# nrf52840-breakout-qwiic-lipo.net
KiCad netlist of a schematic drawn in EAGLE
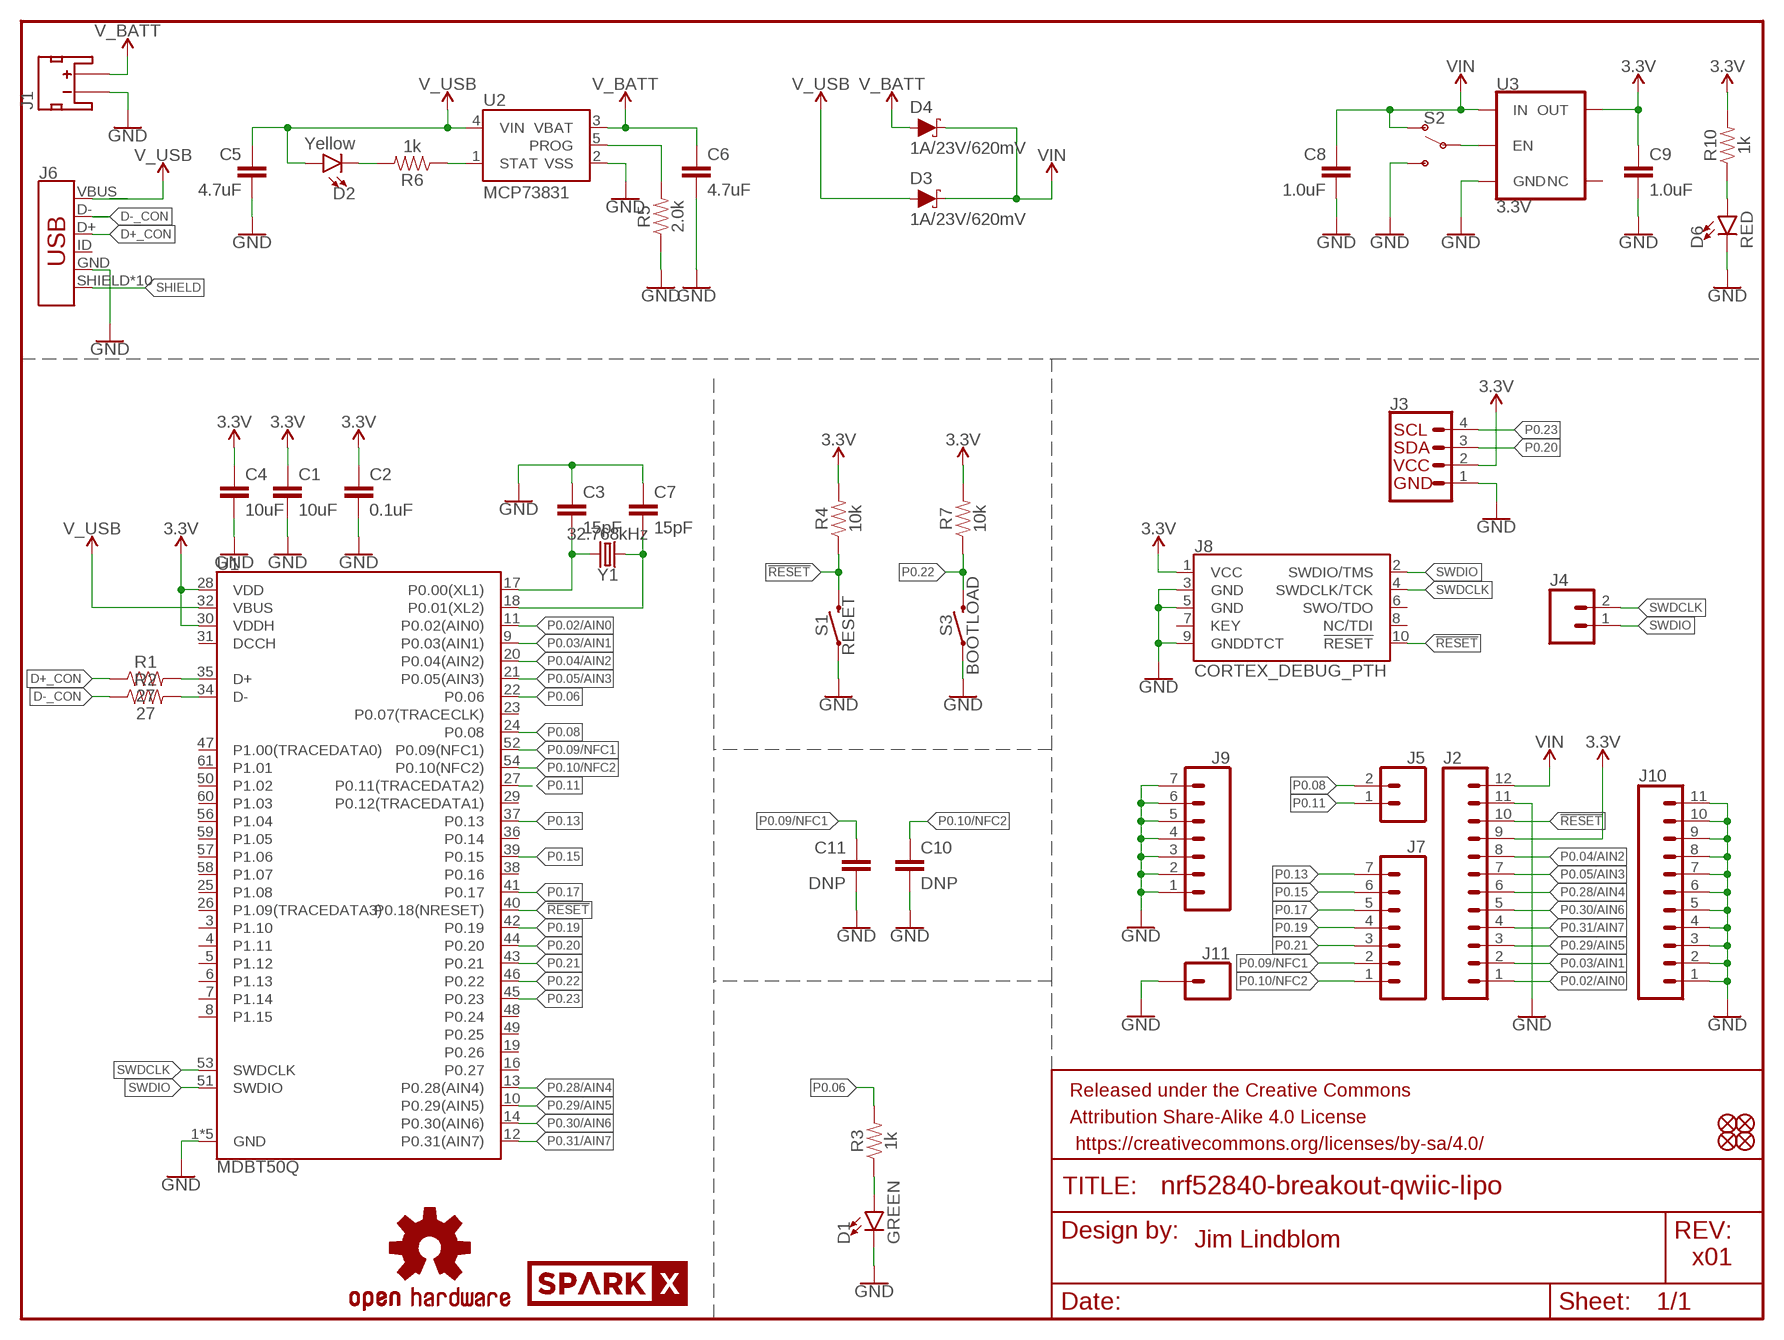
[diagram p0: schematic, sheet 1]

(export (version "E")
  (design (tool "Eeschema 10.0.6"))
  (components
    (comp (ref "C1")
      (value "10uF")
      (footprint "eagle-import:0603")
      (libsource (lib "eagle-import") (part "10UF-0603-6.3V-20%"))
    )
    (comp (ref "C2")
      (value "0.1uF")
      (footprint "eagle-import:0603")
      (libsource (lib "eagle-import") (part "0.1UF-0603-25V-(+80/-20%)"))
    )
    (comp (ref "C3")
      (value "15pF")
      (footprint "eagle-import:0603")
      (libsource (lib "eagle-import") (part "15PF-0603-50V-5%"))
    )
    (comp (ref "C4")
      (value "10uF")
      (footprint "eagle-import:0603")
      (libsource (lib "eagle-import") (part "10UF-0603-6.3V-20%"))
    )
    (comp (ref "C5")
      (value "4.7uF")
      (footprint "eagle-import:0603")
      (libsource (lib "eagle-import") (part "4.7UF-0603-6.3V-(10%)"))
    )
    (comp (ref "C6")
      (value "4.7uF")
      (footprint "eagle-import:0603")
      (libsource (lib "eagle-import") (part "4.7UF-0603-6.3V-(10%)"))
    )
    (comp (ref "C7")
      (value "15pF")
      (footprint "eagle-import:0603")
      (libsource (lib "eagle-import") (part "15PF-0603-50V-5%"))
    )
    (comp (ref "C8")
      (value "1.0uF")
      (footprint "eagle-import:0603")
      (libsource (lib "eagle-import") (part "1.0UF-0603-16V-10%"))
    )
    (comp (ref "C9")
      (value "1.0uF")
      (footprint "eagle-import:0603")
      (libsource (lib "eagle-import") (part "1.0UF-0603-16V-10%"))
    )
    (comp (ref "C10")
      (value "DNP")
      (footprint "eagle-import:0603")
      (libsource (lib "eagle-import") (part "270PF-0603-50V-5%"))
    )
    (comp (ref "C11")
      (value "DNP")
      (footprint "eagle-import:0603")
      (libsource (lib "eagle-import") (part "270PF-0603-50V-5%"))
    )
    (comp (ref "D1")
      (value "GREEN")
      (footprint "eagle-import:LED-0603")
      (libsource (lib "eagle-import") (part "LED-GREEN0603"))
    )
    (comp (ref "D2")
      (value "Yellow")
      (footprint "eagle-import:LED-0603")
      (libsource (lib "eagle-import") (part "LED-YELLOW0603"))
    )
    (comp (ref "D3")
      (value "1A/23V/620mV")
      (footprint "eagle-import:SOD-323")
      (libsource (lib "eagle-import") (part "DIODE-SCHOTTKY-BAT20J"))
    )
    (comp (ref "D4")
      (value "1A/23V/620mV")
      (footprint "eagle-import:SOD-323")
      (libsource (lib "eagle-import") (part "DIODE-SCHOTTKY-BAT20J"))
    )
    (comp (ref "D6")
      (value "RED")
      (footprint "eagle-import:LED-0603")
      (libsource (lib "eagle-import") (part "LED-RED0603"))
    )
    (comp (ref "FD1")
      (value "FIDUCIALUFIDUCIAL")
      (footprint "eagle-import:FIDUCIAL-MICRO")
      (libsource (lib "eagle-import") (part "FIDUCIALUFIDUCIAL"))
    )
    (comp (ref "FD2")
      (value "FIDUCIALUFIDUCIAL")
      (footprint "eagle-import:FIDUCIAL-MICRO")
      (libsource (lib "eagle-import") (part "FIDUCIALUFIDUCIAL"))
    )
    (comp (ref "FD3")
      (value "FIDUCIALUFIDUCIAL")
      (footprint "eagle-import:FIDUCIAL-MICRO")
      (libsource (lib "eagle-import") (part "FIDUCIALUFIDUCIAL"))
    )
    (comp (ref "FD4")
      (value "FIDUCIALUFIDUCIAL")
      (footprint "eagle-import:FIDUCIAL-MICRO")
      (libsource (lib "eagle-import") (part "FIDUCIALUFIDUCIAL"))
    )
    (comp (ref "FRAME1")
      (value "FRAME-LETTER")
      (footprint "eagle-import:CREATIVE_COMMONS")
      (libsource (lib "eagle-import") (part "FRAME-LETTER"))
    )
    (comp (ref "J1")
      (value "JST_2MM_MALESMD")
      (footprint "eagle-import:JST-2-SMD")
      (libsource (lib "eagle-import") (part "JST_2MM_MALESMD"))
    )
    (comp (ref "J2")
      (value "CONN_12NO_SILK")
      (footprint "eagle-import:1X12_NO_SILK")
      (libsource (lib "eagle-import") (part "CONN_12NO_SILK"))
    )
    (comp (ref "J3")
      (value "QWIIC_CONNECTORJS-1MM")
      (footprint "eagle-import:1X04_1MM_RA")
      (libsource (lib "eagle-import") (part "QWIIC_CONNECTORJS-1MM"))
    )
    (comp (ref "J4")
      (value "CONN_021X02_NO_SILK")
      (footprint "eagle-import:1X02_NO_SILK")
      (libsource (lib "eagle-import") (part "CONN_021X02_NO_SILK"))
    )
    (comp (ref "J5")
      (value "CONN_021X02_NO_SILK")
      (footprint "eagle-import:1X02_NO_SILK")
      (libsource (lib "eagle-import") (part "CONN_021X02_NO_SILK"))
    )
    (comp (ref "J6")
      (value "USB_MICRO-B_HALF_PTH_MILL")
      (footprint "eagle-import:USB-MICROB-PTH-MILL")
      (libsource (lib "eagle-import") (part "USB_MICRO-B_HALF_PTH_MILL"))
    )
    (comp (ref "J7")
      (value "CONN_07NO_SILK")
      (footprint "eagle-import:1X07_NO_SILK")
      (libsource (lib "eagle-import") (part "CONN_07NO_SILK"))
    )
    (comp (ref "J8")
      (value "CORTEX_DEBUG_PTH")
      (footprint "eagle-import:2X5-PTH-1.27MM")
      (libsource (lib "eagle-import") (part "CORTEX_DEBUG_PTH"))
    )
    (comp (ref "J9")
      (value "CONN_07NO_SILK")
      (footprint "eagle-import:1X07_NO_SILK")
      (libsource (lib "eagle-import") (part "CONN_07NO_SILK"))
    )
    (comp (ref "J10")
      (value "CONN_111X11_NO_SILK")
      (footprint "eagle-import:1X11_NO_SILK")
      (libsource (lib "eagle-import") (part "CONN_111X11_NO_SILK"))
    )
    (comp (ref "J11")
      (value "CONN_01PTH_NO_SILK_YES_STOP")
      (footprint "eagle-import:1X01_NO_SILK")
      (libsource (lib "eagle-import") (part "CONN_01PTH_NO_SILK_YES_STOP"))
    )
    (comp (ref "LOGO1")
      (value "SPARKX-LOGO3")
      (footprint "eagle-import:SPARKX-SMALL")
      (libsource (lib "eagle-import") (part "SPARKX-LOGO3"))
    )
    (comp (ref "LOGO2")
      (value "OSHW-LOGOM")
      (footprint "eagle-import:OSHW-LOGO-M")
      (libsource (lib "eagle-import") (part "OSHW-LOGOM"))
    )
    (comp (ref "R1")
      (value "27")
      (footprint "eagle-import:0603")
      (libsource (lib "eagle-import") (part "27OHM-0603-1/10W-1%"))
    )
    (comp (ref "R2")
      (value "27")
      (footprint "eagle-import:0603")
      (libsource (lib "eagle-import") (part "27OHM-0603-1/10W-1%"))
    )
    (comp (ref "R3")
      (value "1k")
      (footprint "eagle-import:0603")
      (libsource (lib "eagle-import") (part "1KOHM-0603-1/10W-1%"))
    )
    (comp (ref "R4")
      (value "10k")
      (footprint "eagle-import:0603")
      (libsource (lib "eagle-import") (part "10KOHM-0603-1/10W-1%"))
    )
    (comp (ref "R5")
      (value "2.0k")
      (footprint "eagle-import:0603")
      (libsource (lib "eagle-import") (part "2.0KOHM-0603-1/10W-5%"))
    )
    (comp (ref "R6")
      (value "1k")
      (footprint "eagle-import:0603")
      (libsource (lib "eagle-import") (part "1KOHM-0603-1/10W-1%"))
    )
    (comp (ref "R7")
      (value "10k")
      (footprint "eagle-import:0603")
      (libsource (lib "eagle-import") (part "10KOHM-0603-1/10W-1%"))
    )
    (comp (ref "R10")
      (value "1k")
      (footprint "eagle-import:0603")
      (libsource (lib "eagle-import") (part "1KOHM-0603-1/10W-1%"))
    )
    (comp (ref "S1")
      (value "RESET")
      (footprint "eagle-import:TACTILE_SWITCH_SMD_RIGHT_ANGLE")
      (libsource (lib "eagle-import") (part "MOMENTARY-SWITCH-SPST-SMD-RIGHT-ANGLE"))
    )
    (comp (ref "S2")
      (value "SWITCH-SPDT-SMD-RIGHT-ANGLE")
      (footprint "eagle-import:SWITCH_SPST_SMD_A")
      (libsource (lib "eagle-import") (part "SWITCH-SPDT-SMD-RIGHT-ANGLE"))
    )
    (comp (ref "S3")
      (value "BOOTLOAD")
      (footprint "eagle-import:TACTILE_SWITCH_SMD_RIGHT_ANGLE")
      (libsource (lib "eagle-import") (part "MOMENTARY-SWITCH-SPST-SMD-RIGHT-ANGLE"))
    )
    (comp (ref "U1")
      (value "MDBT50Q")
      (footprint "eagle-import:MDBT50Q")
      (libsource (lib "eagle-import") (part "MDBT50Q"))
    )
    (comp (ref "U2")
      (value "MCP73831")
      (footprint "eagle-import:SOT23-5")
      (libsource (lib "eagle-import") (part "MCP73831"))
    )
    (comp (ref "U3")
      (value "3.3V")
      (footprint "eagle-import:SOT23-5")
      (libsource (lib "eagle-import") (part "V_REG_AP2112K-3.3V"))
    )
    (comp (ref "Y1")
      (value "32.768kHz")
      (footprint "eagle-import:CRYSTAL-SMD-3.2X1.5MM")
      (libsource (lib "eagle-import") (part "CRYSTAL-32.768KHZSMD-3.2X1.5"))
    )
  )
  (nets
    (net (code "1") (name "/~{RESET}") (class "Default")
      (node (ref "J2") (pin "10") (pinfunction "10_10") (pintype "passive"))
      (node (ref "J8") (pin "10") (pinfunction "~{RESET}_10") (pintype "bidirectional"))
      (node (ref "R4") (pin "1") (pinfunction "1_1") (pintype "passive"))
      (node (ref "S1") (pin "2") (pinfunction "2_2") (pintype "passive"))
      (node (ref "U1") (pin "40") (pinfunction "P0.18(NRESET)_40") (pintype "bidirectional"))
    )
    (net (code "2") (name "3.3V") (class "Default")
      (node (ref "C1") (pin "1") (pinfunction "1_1") (pintype "passive"))
      (node (ref "C2") (pin "1") (pinfunction "1_1") (pintype "passive"))
      (node (ref "C4") (pin "1") (pinfunction "1_1") (pintype "passive"))
      (node (ref "C9") (pin "1") (pinfunction "1_1") (pintype "passive"))
      (node (ref "J2") (pin "9") (pinfunction "9_9") (pintype "passive"))
      (node (ref "J3") (pin "2") (pinfunction "2_2") (pintype "power_in"))
      (node (ref "J8") (pin "1") (pinfunction "VCC_1") (pintype "bidirectional"))
      (node (ref "R10") (pin "2") (pinfunction "2_2") (pintype "passive"))
      (node (ref "R4") (pin "2") (pinfunction "2_2") (pintype "passive"))
      (node (ref "R7") (pin "2") (pinfunction "2_2") (pintype "passive"))
      (node (ref "U1") (pin "28") (pinfunction "VDD_28") (pintype "bidirectional"))
      (node (ref "U1") (pin "30") (pinfunction "VDDH_30") (pintype "bidirectional"))
      (node (ref "U3") (pin "5") (pinfunction "OUT_5") (pintype "passive"))
    )
    (net (code "3") (name "D+_CON") (class "Default")
      (node (ref "J6") (pin "D+") (pinfunction "D+_D+") (pintype "bidirectional"))
      (node (ref "R1") (pin "1") (pinfunction "1_1") (pintype "passive"))
    )
    (net (code "4") (name "D-_CON") (class "Default")
      (node (ref "J6") (pin "D-") (pinfunction "D-_D-") (pintype "bidirectional"))
      (node (ref "R2") (pin "1") (pinfunction "1_1") (pintype "passive"))
    )
    (net (code "5") (name "GND") (class "Default")
      (node (ref "C1") (pin "2") (pinfunction "2_2") (pintype "passive"))
      (node (ref "C10") (pin "2") (pinfunction "2_2") (pintype "passive"))
      (node (ref "C11") (pin "2") (pinfunction "2_2") (pintype "passive"))
      (node (ref "C2") (pin "2") (pinfunction "2_2") (pintype "passive"))
      (node (ref "C3") (pin "1") (pinfunction "1_1") (pintype "passive"))
      (node (ref "C4") (pin "2") (pinfunction "2_2") (pintype "passive"))
      (node (ref "C5") (pin "2") (pinfunction "2_2") (pintype "passive"))
      (node (ref "C6") (pin "2") (pinfunction "2_2") (pintype "passive"))
      (node (ref "C7") (pin "1") (pinfunction "1_1") (pintype "passive"))
      (node (ref "C8") (pin "2") (pinfunction "2_2") (pintype "passive"))
      (node (ref "C9") (pin "2") (pinfunction "2_2") (pintype "passive"))
      (node (ref "D1") (pin "C") (pinfunction "C_C") (pintype "passive"))
      (node (ref "D6") (pin "C") (pinfunction "C_C") (pintype "passive"))
      (node (ref "J1") (pin "1") (pinfunction "-_1") (pintype "bidirectional"))
      (node (ref "J10") (pin "1") (pinfunction "1_1") (pintype "passive"))
      (node (ref "J10") (pin "10") (pinfunction "10_10") (pintype "passive"))
      (node (ref "J10") (pin "11") (pinfunction "11_11") (pintype "passive"))
      (node (ref "J10") (pin "2") (pinfunction "2_2") (pintype "passive"))
      (node (ref "J10") (pin "3") (pinfunction "3_3") (pintype "passive"))
      (node (ref "J10") (pin "4") (pinfunction "4_4") (pintype "passive"))
      (node (ref "J10") (pin "5") (pinfunction "5_5") (pintype "passive"))
      (node (ref "J10") (pin "6") (pinfunction "6_6") (pintype "passive"))
      (node (ref "J10") (pin "7") (pinfunction "7_7") (pintype "passive"))
      (node (ref "J10") (pin "8") (pinfunction "8_8") (pintype "passive"))
      (node (ref "J10") (pin "9") (pinfunction "9_9") (pintype "passive"))
      (node (ref "J11") (pin "1") (pinfunction "1_1") (pintype "passive"))
      (node (ref "J2") (pin "11") (pinfunction "11_11") (pintype "passive"))
      (node (ref "J3") (pin "1") (pinfunction "1_1") (pintype "power_in"))
      (node (ref "J6") (pin "GND") (pinfunction "GND_GND") (pintype "power_in"))
      (node (ref "J8") (pin "3") (pinfunction "GND_3") (pintype "bidirectional"))
      (node (ref "J8") (pin "5") (pinfunction "GND_5") (pintype "bidirectional"))
      (node (ref "J8") (pin "9") (pinfunction "GNDDTCT_9") (pintype "bidirectional"))
      (node (ref "J9") (pin "1") (pinfunction "1_1") (pintype "passive"))
      (node (ref "J9") (pin "2") (pinfunction "2_2") (pintype "passive"))
      (node (ref "J9") (pin "3") (pinfunction "3_3") (pintype "passive"))
      (node (ref "J9") (pin "4") (pinfunction "4_4") (pintype "passive"))
      (node (ref "J9") (pin "5") (pinfunction "5_5") (pintype "passive"))
      (node (ref "J9") (pin "6") (pinfunction "6_6") (pintype "passive"))
      (node (ref "J9") (pin "7") (pinfunction "7_7") (pintype "passive"))
      (node (ref "R5") (pin "1") (pinfunction "1_1") (pintype "passive"))
      (node (ref "S1") (pin "1") (pinfunction "1_1") (pintype "passive"))
      (node (ref "S2") (pin "3") (pinfunction "S_3") (pintype "passive"))
      (node (ref "S3") (pin "1") (pinfunction "1_1") (pintype "passive"))
      (node (ref "U1") (pin "1") (pinfunction "GND_1") (pintype "bidirectional"))
      (node (ref "U1") (pin "15") (pinfunction "GND_15") (pintype "bidirectional"))
      (node (ref "U1") (pin "2") (pinfunction "GND_2") (pintype "bidirectional"))
      (node (ref "U1") (pin "33") (pinfunction "GND_33") (pintype "bidirectional"))
      (node (ref "U1") (pin "55") (pinfunction "GND_55") (pintype "bidirectional"))
      (node (ref "U2") (pin "2") (pinfunction "VSS_2") (pintype "power_in"))
      (node (ref "U3") (pin "2") (pinfunction "GND_2") (pintype "input"))
    )
    (net (code "6") (name "Net-(D1-PadA)") (class "Default")
      (node (ref "D1") (pin "A") (pinfunction "A_A") (pintype "passive"))
      (node (ref "R3") (pin "1") (pinfunction "1_1") (pintype "passive"))
    )
    (net (code "7") (name "Net-(D2-PadC)") (class "Default")
      (node (ref "D2") (pin "C") (pinfunction "C_C") (pintype "passive"))
      (node (ref "R6") (pin "2") (pinfunction "2_2") (pintype "passive"))
    )
    (net (code "8") (name "Net-(D6-PadA)") (class "Default")
      (node (ref "D6") (pin "A") (pinfunction "A_A") (pintype "passive"))
      (node (ref "R10") (pin "1") (pinfunction "1_1") (pintype "passive"))
    )
    (net (code "9") (name "Net-(S2-P)") (class "Default")
      (node (ref "S2") (pin "2") (pinfunction "P_2") (pintype "passive"))
      (node (ref "U3") (pin "3") (pinfunction "EN_3") (pintype "input"))
    )
    (net (code "10") (name "Net-(U1-D+)") (class "Default")
      (node (ref "R1") (pin "2") (pinfunction "2_2") (pintype "passive"))
      (node (ref "U1") (pin "35") (pinfunction "D+_35") (pintype "bidirectional"))
    )
    (net (code "11") (name "Net-(U1-D-)") (class "Default")
      (node (ref "R2") (pin "2") (pinfunction "2_2") (pintype "passive"))
      (node (ref "U1") (pin "34") (pinfunction "D-_34") (pintype "bidirectional"))
    )
    (net (code "12") (name "Net-(U1-P0.00(XL1))") (class "Default")
      (node (ref "C3") (pin "2") (pinfunction "2_2") (pintype "passive"))
      (node (ref "U1") (pin "17") (pinfunction "P0.00(XL1)_17") (pintype "bidirectional"))
      (node (ref "Y1") (pin "P$2") (pinfunction "2_P$2") (pintype "passive"))
    )
    (net (code "13") (name "Net-(U1-P0.01(XL2))") (class "Default")
      (node (ref "C7") (pin "2") (pinfunction "2_2") (pintype "passive"))
      (node (ref "U1") (pin "18") (pinfunction "P0.01(XL2)_18") (pintype "bidirectional"))
      (node (ref "Y1") (pin "P$1") (pinfunction "1_P$1") (pintype "passive"))
    )
    (net (code "14") (name "Net-(U2-PROG)") (class "Default")
      (node (ref "R5") (pin "2") (pinfunction "2_2") (pintype "passive"))
      (node (ref "U2") (pin "5") (pinfunction "PROG_5") (pintype "input"))
    )
    (net (code "15") (name "Net-(U2-STAT)") (class "Default")
      (node (ref "R6") (pin "1") (pinfunction "1_1") (pintype "passive"))
      (node (ref "U2") (pin "1") (pinfunction "STAT_1") (pintype "output"))
    )
    (net (code "16") (name "P0.02{slash}AIN0") (class "Default")
      (node (ref "J2") (pin "1") (pinfunction "1_1") (pintype "passive"))
      (node (ref "U1") (pin "11") (pinfunction "P0.02(AIN0)_11") (pintype "bidirectional"))
    )
    (net (code "17") (name "P0.03{slash}AIN1") (class "Default")
      (node (ref "J2") (pin "2") (pinfunction "2_2") (pintype "passive"))
      (node (ref "U1") (pin "9") (pinfunction "P0.03(AIN1)_9") (pintype "bidirectional"))
    )
    (net (code "18") (name "P0.04{slash}AIN2") (class "Default")
      (node (ref "J2") (pin "8") (pinfunction "8_8") (pintype "passive"))
      (node (ref "U1") (pin "20") (pinfunction "P0.04(AIN2)_20") (pintype "bidirectional"))
    )
    (net (code "19") (name "P0.05{slash}AIN3") (class "Default")
      (node (ref "J2") (pin "7") (pinfunction "7_7") (pintype "passive"))
      (node (ref "U1") (pin "21") (pinfunction "P0.05(AIN3)_21") (pintype "bidirectional"))
    )
    (net (code "20") (name "P0.06") (class "Default")
      (node (ref "R3") (pin "2") (pinfunction "2_2") (pintype "passive"))
      (node (ref "U1") (pin "22") (pinfunction "P0.06_22") (pintype "bidirectional"))
    )
    (net (code "21") (name "P0.08") (class "Default")
      (node (ref "J5") (pin "2") (pinfunction "2_2") (pintype "passive"))
      (node (ref "U1") (pin "24") (pinfunction "P0.08_24") (pintype "bidirectional"))
    )
    (net (code "22") (name "P0.09{slash}NFC1") (class "Default")
      (node (ref "C11") (pin "1") (pinfunction "1_1") (pintype "passive"))
      (node (ref "J7") (pin "2") (pinfunction "2_2") (pintype "passive"))
      (node (ref "U1") (pin "52") (pinfunction "P0.09(NFC1)_52") (pintype "bidirectional"))
    )
    (net (code "23") (name "P0.10{slash}NFC2") (class "Default")
      (node (ref "C10") (pin "1") (pinfunction "1_1") (pintype "passive"))
      (node (ref "J7") (pin "1") (pinfunction "1_1") (pintype "passive"))
      (node (ref "U1") (pin "54") (pinfunction "P0.10(NFC2)_54") (pintype "bidirectional"))
    )
    (net (code "24") (name "P0.11") (class "Default")
      (node (ref "J5") (pin "1") (pinfunction "1_1") (pintype "passive"))
      (node (ref "U1") (pin "27") (pinfunction "P0.11(TRACEDATA2)_27") (pintype "bidirectional"))
    )
    (net (code "25") (name "P0.13") (class "Default")
      (node (ref "J7") (pin "7") (pinfunction "7_7") (pintype "passive"))
      (node (ref "U1") (pin "37") (pinfunction "P0.13_37") (pintype "bidirectional"))
    )
    (net (code "26") (name "P0.15") (class "Default")
      (node (ref "J7") (pin "6") (pinfunction "6_6") (pintype "passive"))
      (node (ref "U1") (pin "39") (pinfunction "P0.15_39") (pintype "bidirectional"))
    )
    (net (code "27") (name "P0.17") (class "Default")
      (node (ref "J7") (pin "5") (pinfunction "5_5") (pintype "passive"))
      (node (ref "U1") (pin "41") (pinfunction "P0.17_41") (pintype "bidirectional"))
    )
    (net (code "28") (name "P0.19") (class "Default")
      (node (ref "J7") (pin "4") (pinfunction "4_4") (pintype "passive"))
      (node (ref "U1") (pin "42") (pinfunction "P0.19_42") (pintype "bidirectional"))
    )
    (net (code "29") (name "P0.20") (class "Default")
      (node (ref "J3") (pin "3") (pinfunction "3_3") (pintype "passive"))
      (node (ref "U1") (pin "44") (pinfunction "P0.20_44") (pintype "bidirectional"))
    )
    (net (code "30") (name "P0.21") (class "Default")
      (node (ref "J7") (pin "3") (pinfunction "3_3") (pintype "passive"))
      (node (ref "U1") (pin "43") (pinfunction "P0.21_43") (pintype "bidirectional"))
    )
    (net (code "31") (name "P0.22") (class "Default")
      (node (ref "R7") (pin "1") (pinfunction "1_1") (pintype "passive"))
      (node (ref "S3") (pin "2") (pinfunction "2_2") (pintype "passive"))
      (node (ref "U1") (pin "46") (pinfunction "P0.22_46") (pintype "bidirectional"))
    )
    (net (code "32") (name "P0.23") (class "Default")
      (node (ref "J3") (pin "4") (pinfunction "4_4") (pintype "passive"))
      (node (ref "U1") (pin "45") (pinfunction "P0.23_45") (pintype "bidirectional"))
    )
    (net (code "33") (name "P0.28{slash}AIN4") (class "Default")
      (node (ref "J2") (pin "6") (pinfunction "6_6") (pintype "passive"))
      (node (ref "U1") (pin "13") (pinfunction "P0.28(AIN4)_13") (pintype "bidirectional"))
    )
    (net (code "34") (name "P0.29{slash}AIN5") (class "Default")
      (node (ref "J2") (pin "3") (pinfunction "3_3") (pintype "passive"))
      (node (ref "U1") (pin "10") (pinfunction "P0.29(AIN5)_10") (pintype "bidirectional"))
    )
    (net (code "35") (name "P0.30{slash}AIN6") (class "Default")
      (node (ref "J2") (pin "5") (pinfunction "5_5") (pintype "passive"))
      (node (ref "U1") (pin "14") (pinfunction "P0.30(AIN6)_14") (pintype "bidirectional"))
    )
    (net (code "36") (name "P0.31{slash}AIN7") (class "Default")
      (node (ref "J2") (pin "4") (pinfunction "4_4") (pintype "passive"))
      (node (ref "U1") (pin "12") (pinfunction "P0.31(AIN7)_12") (pintype "bidirectional"))
    )
    (net (code "37") (name "SHIELD") (class "Default")
      (node (ref "J6") (pin "SHIELD") (pinfunction "SHIELD_SHIELD") (pintype "bidirectional"))
      (node (ref "J6") (pin "SHIELD10") (pinfunction "SHIELD_SHIELD10") (pintype "bidirectional"))
      (node (ref "J6") (pin "SHIELD2") (pinfunction "SHIELD_SHIELD2") (pintype "bidirectional"))
      (node (ref "J6") (pin "SHIELD3") (pinfunction "SHIELD_SHIELD3") (pintype "bidirectional"))
      (node (ref "J6") (pin "SHIELD4") (pinfunction "SHIELD_SHIELD4") (pintype "bidirectional"))
      (node (ref "J6") (pin "SHIELD5") (pinfunction "SHIELD_SHIELD5") (pintype "bidirectional"))
      (node (ref "J6") (pin "SHIELD6") (pinfunction "SHIELD_SHIELD6") (pintype "bidirectional"))
      (node (ref "J6") (pin "SHIELD7") (pinfunction "SHIELD_SHIELD7") (pintype "bidirectional"))
      (node (ref "J6") (pin "SHIELD8") (pinfunction "SHIELD_SHIELD8") (pintype "bidirectional"))
      (node (ref "J6") (pin "SHIELD9") (pinfunction "SHIELD_SHIELD9") (pintype "bidirectional"))
    )
    (net (code "38") (name "SWDCLK") (class "Default")
      (node (ref "J4") (pin "2") (pinfunction "2_2") (pintype "passive"))
      (node (ref "J8") (pin "4") (pinfunction "SWDCLK/TCK_4") (pintype "bidirectional"))
      (node (ref "U1") (pin "53") (pinfunction "SWDCLK_53") (pintype "bidirectional"))
    )
    (net (code "39") (name "SWDIO") (class "Default")
      (node (ref "J4") (pin "1") (pinfunction "1_1") (pintype "passive"))
      (node (ref "J8") (pin "2") (pinfunction "SWDIO/TMS_2") (pintype "bidirectional"))
      (node (ref "U1") (pin "51") (pinfunction "SWDIO_51") (pintype "bidirectional"))
    )
    (net (code "40") (name "VIN") (class "Default")
      (node (ref "C8") (pin "1") (pinfunction "1_1") (pintype "passive"))
      (node (ref "D3") (pin "C") (pinfunction "C_C") (pintype "passive"))
      (node (ref "D4") (pin "C") (pinfunction "C_C") (pintype "passive"))
      (node (ref "J2") (pin "12") (pinfunction "12_12") (pintype "passive"))
      (node (ref "S2") (pin "1") (pinfunction "O_1") (pintype "passive"))
      (node (ref "U3") (pin "1") (pinfunction "IN_1") (pintype "input"))
    )
    (net (code "41") (name "V_BATT") (class "Default")
      (node (ref "C6") (pin "1") (pinfunction "1_1") (pintype "passive"))
      (node (ref "D4") (pin "A") (pinfunction "A_A") (pintype "passive"))
      (node (ref "J1") (pin "2") (pinfunction "+_2") (pintype "bidirectional"))
      (node (ref "U2") (pin "3") (pinfunction "VBAT_3") (pintype "power_in"))
    )
    (net (code "42") (name "V_USB") (class "Default")
      (node (ref "C5") (pin "1") (pinfunction "1_1") (pintype "passive"))
      (node (ref "D2") (pin "A") (pinfunction "A_A") (pintype "passive"))
      (node (ref "D3") (pin "A") (pinfunction "A_A") (pintype "passive"))
      (node (ref "J6") (pin "VBUS") (pinfunction "VBUS_VBUS") (pintype "power_in"))
      (node (ref "U1") (pin "32") (pinfunction "VBUS_32") (pintype "bidirectional"))
      (node (ref "U2") (pin "4") (pinfunction "VIN_4") (pintype "power_in"))
    )
    (net (code "43") (name "unconnected-(J6-PadID)") (class "Default")
      (node (ref "J6") (pin "ID") (pinfunction "ID_ID") (pintype "bidirectional"))
    )
    (net (code "44") (name "unconnected-(J8-KEY-Pad7)") (class "Default")
      (node (ref "J8") (pin "7") (pinfunction "KEY_7") (pintype "bidirectional"))
    )
    (net (code "45") (name "unconnected-(J8-NC{slash}TDI-Pad8)") (class "Default")
      (node (ref "J8") (pin "8") (pinfunction "NC/TDI_8") (pintype "bidirectional"))
    )
    (net (code "46") (name "unconnected-(J8-SWO{slash}TDO-Pad6)") (class "Default")
      (node (ref "J8") (pin "6") (pinfunction "SWO/TDO_6") (pintype "bidirectional"))
    )
    (net (code "47") (name "unconnected-(U1-DCCH-Pad31)") (class "Default")
      (node (ref "U1") (pin "31") (pinfunction "DCCH_31") (pintype "bidirectional"))
    )
    (net (code "48") (name "unconnected-(U1-P0.07(TRACECLK)-Pad23)") (class "Default")
      (node (ref "U1") (pin "23") (pinfunction "P0.07(TRACECLK)_23") (pintype "bidirectional"))
    )
    (net (code "49") (name "unconnected-(U1-P0.12(TRACEDATA1)-Pad29)") (class "Default")
      (node (ref "U1") (pin "29") (pinfunction "P0.12(TRACEDATA1)_29") (pintype "bidirectional"))
    )
    (net (code "50") (name "unconnected-(U1-P0.14-Pad36)") (class "Default")
      (node (ref "U1") (pin "36") (pinfunction "P0.14_36") (pintype "bidirectional"))
    )
    (net (code "51") (name "unconnected-(U1-P0.16-Pad38)") (class "Default")
      (node (ref "U1") (pin "38") (pinfunction "P0.16_38") (pintype "bidirectional"))
    )
    (net (code "52") (name "unconnected-(U1-P0.24-Pad48)") (class "Default")
      (node (ref "U1") (pin "48") (pinfunction "P0.24_48") (pintype "bidirectional"))
    )
    (net (code "53") (name "unconnected-(U1-P0.25-Pad49)") (class "Default")
      (node (ref "U1") (pin "49") (pinfunction "P0.25_49") (pintype "bidirectional"))
    )
    (net (code "54") (name "unconnected-(U1-P0.26-Pad19)") (class "Default")
      (node (ref "U1") (pin "19") (pinfunction "P0.26_19") (pintype "bidirectional"))
    )
    (net (code "55") (name "unconnected-(U1-P0.27-Pad16)") (class "Default")
      (node (ref "U1") (pin "16") (pinfunction "P0.27_16") (pintype "bidirectional"))
    )
    (net (code "56") (name "unconnected-(U1-P1.00(TRACEDATA0)-Pad47)") (class "Default")
      (node (ref "U1") (pin "47") (pinfunction "P1.00(TRACEDATA0)_47") (pintype "bidirectional"))
    )
    (net (code "57") (name "unconnected-(U1-P1.01-Pad61)") (class "Default")
      (node (ref "U1") (pin "61") (pinfunction "P1.01_61") (pintype "bidirectional"))
    )
    (net (code "58") (name "unconnected-(U1-P1.02-Pad50)") (class "Default")
      (node (ref "U1") (pin "50") (pinfunction "P1.02_50") (pintype "bidirectional"))
    )
    (net (code "59") (name "unconnected-(U1-P1.03-Pad60)") (class "Default")
      (node (ref "U1") (pin "60") (pinfunction "P1.03_60") (pintype "bidirectional"))
    )
    (net (code "60") (name "unconnected-(U1-P1.04-Pad56)") (class "Default")
      (node (ref "U1") (pin "56") (pinfunction "P1.04_56") (pintype "bidirectional"))
    )
    (net (code "61") (name "unconnected-(U1-P1.05-Pad59)") (class "Default")
      (node (ref "U1") (pin "59") (pinfunction "P1.05_59") (pintype "bidirectional"))
    )
    (net (code "62") (name "unconnected-(U1-P1.06-Pad57)") (class "Default")
      (node (ref "U1") (pin "57") (pinfunction "P1.06_57") (pintype "bidirectional"))
    )
    (net (code "63") (name "unconnected-(U1-P1.07-Pad58)") (class "Default")
      (node (ref "U1") (pin "58") (pinfunction "P1.07_58") (pintype "bidirectional"))
    )
    (net (code "64") (name "unconnected-(U1-P1.08-Pad25)") (class "Default")
      (node (ref "U1") (pin "25") (pinfunction "P1.08_25") (pintype "bidirectional"))
    )
    (net (code "65") (name "unconnected-(U1-P1.09(TRACEDATA3)-Pad26)") (class "Default")
      (node (ref "U1") (pin "26") (pinfunction "P1.09(TRACEDATA3)_26") (pintype "bidirectional"))
    )
    (net (code "66") (name "unconnected-(U1-P1.10-Pad3)") (class "Default")
      (node (ref "U1") (pin "3") (pinfunction "P1.10_3") (pintype "bidirectional"))
    )
    (net (code "67") (name "unconnected-(U1-P1.11-Pad4)") (class "Default")
      (node (ref "U1") (pin "4") (pinfunction "P1.11_4") (pintype "bidirectional"))
    )
    (net (code "68") (name "unconnected-(U1-P1.12-Pad5)") (class "Default")
      (node (ref "U1") (pin "5") (pinfunction "P1.12_5") (pintype "bidirectional"))
    )
    (net (code "69") (name "unconnected-(U1-P1.13-Pad6)") (class "Default")
      (node (ref "U1") (pin "6") (pinfunction "P1.13_6") (pintype "bidirectional"))
    )
    (net (code "70") (name "unconnected-(U1-P1.14-Pad7)") (class "Default")
      (node (ref "U1") (pin "7") (pinfunction "P1.14_7") (pintype "bidirectional"))
    )
    (net (code "71") (name "unconnected-(U1-P1.15-Pad8)") (class "Default")
      (node (ref "U1") (pin "8") (pinfunction "P1.15_8") (pintype "bidirectional"))
    )
    (net (code "72") (name "unconnected-(U3-NC-Pad4)") (class "Default")
      (node (ref "U3") (pin "4") (pinfunction "NC_4") (pintype "no_connect"))
    )
  )
)
